# schematic.net
KiCad netlist of a schematic drawn in Altium Designer
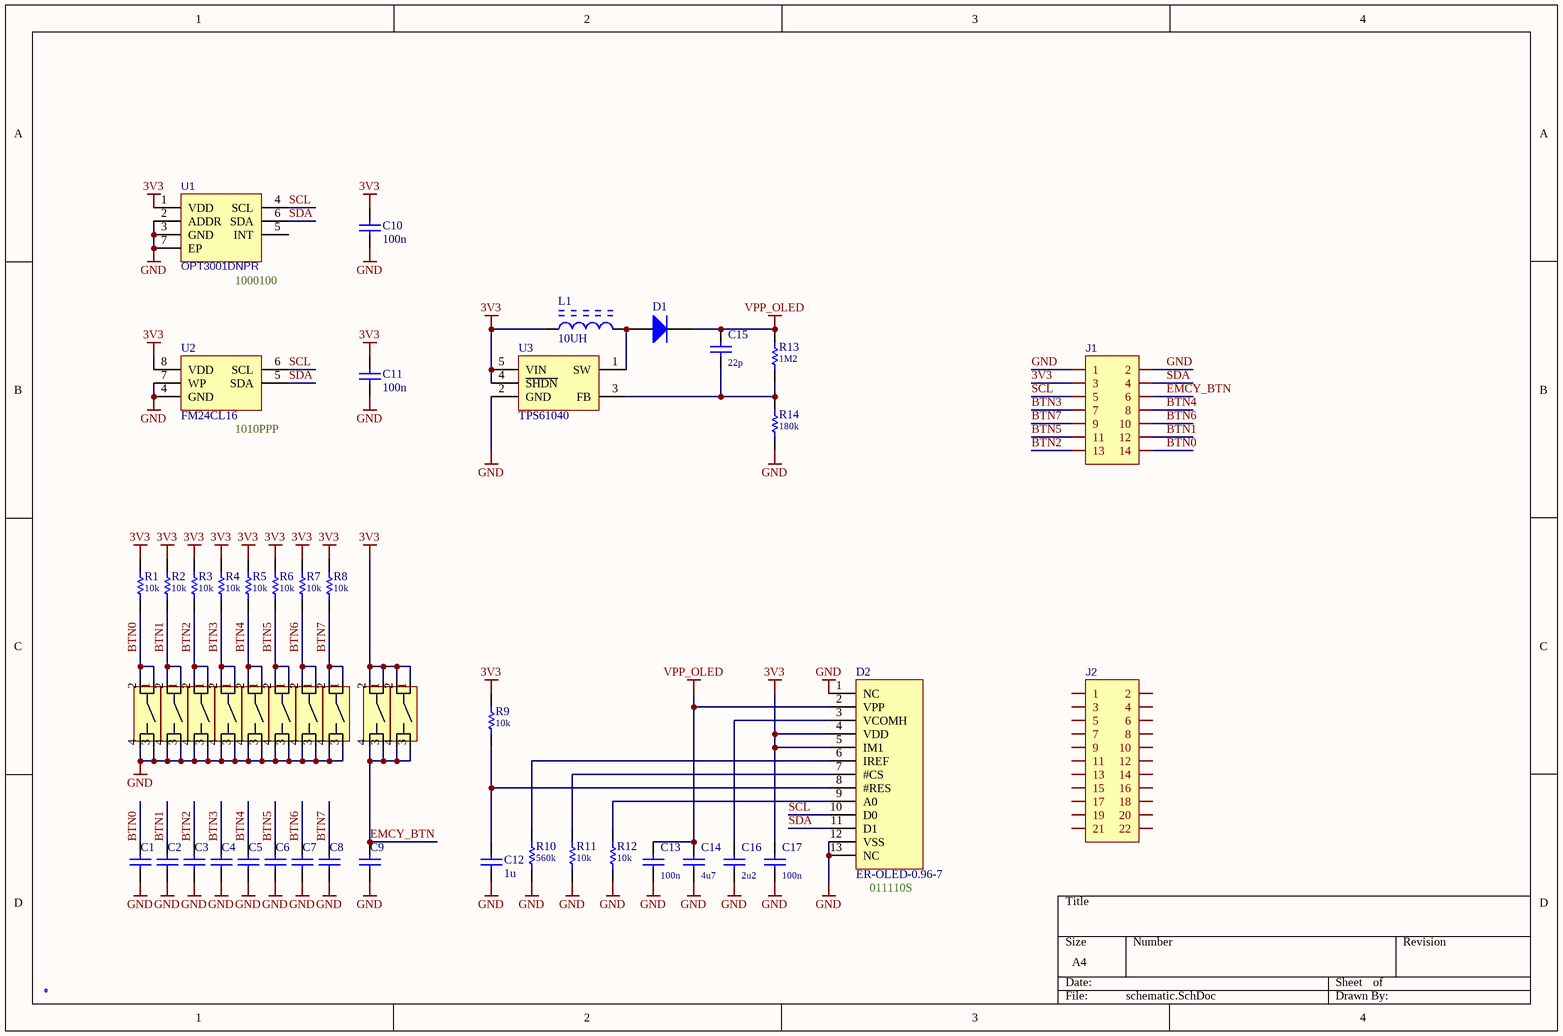
[diagram p0: schematic.SchDoc]

(export (version "E")
  (design (tool "Eeschema 10.0.6"))
  (components
    (comp (ref "C1")
      (value "100n")
      (footprint "C0402")
      (libsource (lib "Miscellaneous Devices") (part "Cap"))
    )
    (comp (ref "C2")
      (value "100n")
      (footprint "C0402")
      (libsource (lib "Miscellaneous Devices") (part "Cap"))
    )
    (comp (ref "C3")
      (value "100n")
      (footprint "C0402")
      (libsource (lib "Miscellaneous Devices") (part "Cap"))
    )
    (comp (ref "C4")
      (value "100n")
      (footprint "C0402")
      (libsource (lib "Miscellaneous Devices") (part "Cap"))
    )
    (comp (ref "C5")
      (value "100n")
      (footprint "C0402")
      (libsource (lib "Miscellaneous Devices") (part "Cap"))
    )
    (comp (ref "C6")
      (value "100n")
      (footprint "C0402")
      (libsource (lib "Miscellaneous Devices") (part "Cap"))
    )
    (comp (ref "C7")
      (value "100n")
      (footprint "C0402")
      (libsource (lib "Miscellaneous Devices") (part "Cap"))
    )
    (comp (ref "C8")
      (value "100n")
      (footprint "C0402")
      (libsource (lib "Miscellaneous Devices") (part "Cap"))
    )
    (comp (ref "C9")
      (value "100n")
      (footprint "C0402")
      (libsource (lib "Miscellaneous Devices") (part "Cap"))
    )
    (comp (ref "C10")
      (value "100n")
      (footprint "C0402")
      (libsource (lib "Miscellaneous Devices") (part "Cap"))
    )
    (comp (ref "C11")
      (value "100n")
      (footprint "C0402")
      (libsource (lib "Miscellaneous Devices") (part "Cap"))
    )
    (comp (ref "C12") (value "1u") (footprint "C0603") (libsource (lib "Miscellaneous Devices") (part "Cap")))
    (comp (ref "C13")
      (value "100n")
      (footprint "C0603")
      (libsource (lib "Miscellaneous Devices") (part "CAP"))
    )
    (comp (ref "C14")
      (value "4u7")
      (footprint "C0805")
      (libsource (lib "Miscellaneous Devices") (part "CAP"))
    )
    (comp (ref "C15")
      (value "22p")
      (footprint "C0603")
      (libsource (lib "Miscellaneous Devices") (part "CAP"))
    )
    (comp (ref "C16")
      (value "2u2")
      (footprint "C0603")
      (libsource (lib "Miscellaneous Devices") (part "CAP"))
    )
    (comp (ref "C17")
      (value "100n")
      (footprint "C0603")
      (libsource (lib "Miscellaneous Devices") (part "CAP"))
    )
    (comp (ref "D1")
      (value "~")
      (footprint "SOD-323")
      (libsource (lib "Miscellaneous Devices") (part "US1M-13-F"))
    )
    (comp (ref "D2")
      (value "ER-OLED-0.96-7")
      (footprint "pico_oled_1.3")
      (libsource (lib "Schlib2") (part "Component_1"))
    )
    (comp (ref "J1") (value "~") (footprint "HDR-2X7-P2.00") (libsource (lib "Schlib1") (part "HDR 2X7")))
    (comp (ref "J2") (value "~") (footprint "HDR-2X11-P2.00") (libsource (lib "Schlib1") (part "HDR 2X11")))
    (comp (ref "L1")
      (value "10UH")
      (footprint "IND_SDE0403A_4X4MM")
      (description "10uH 1A 2520")
      (libsource (lib "Miscellaneous Devices") (part "SRN3015-100M"))
    )
    (comp (ref "LOGO1") (value "LOGO") (footprint "LOGO") (libsource (lib "Schlib1") (part "LOGO")))
    (comp (ref "R1") (value "10k") (footprint "R0603") (libsource (lib "Miscellaneous Devices") (part "RES")))
    (comp (ref "R2") (value "10k") (footprint "R0603") (libsource (lib "Miscellaneous Devices") (part "RES")))
    (comp (ref "R3") (value "10k") (footprint "R0603") (libsource (lib "Miscellaneous Devices") (part "RES")))
    (comp (ref "R4") (value "10k") (footprint "R0603") (libsource (lib "Miscellaneous Devices") (part "RES")))
    (comp (ref "R5") (value "10k") (footprint "R0603") (libsource (lib "Miscellaneous Devices") (part "RES")))
    (comp (ref "R6") (value "10k") (footprint "R0603") (libsource (lib "Miscellaneous Devices") (part "RES")))
    (comp (ref "R7") (value "10k") (footprint "R0603") (libsource (lib "Miscellaneous Devices") (part "RES")))
    (comp (ref "R8") (value "10k") (footprint "R0603") (libsource (lib "Miscellaneous Devices") (part "RES")))
    (comp (ref "R9")
      (value "10k")
      (footprint "R0603")
      (description "10k 0603")
      (libsource (lib "RR_Passive") (part "RES"))
    )
    (comp (ref "R10")
      (value "560k")
      (footprint "R0603")
      (libsource (lib "Miscellaneous Devices") (part "RES"))
    )
    (comp (ref "R11")
      (value "10k")
      (footprint "R0603")
      (description "10k 0603")
      (libsource (lib "RR_Passive") (part "RES"))
    )
    (comp (ref "R12")
      (value "10k")
      (footprint "R0603")
      (description "10k 0603")
      (libsource (lib "RR_Passive") (part "RES"))
    )
    (comp (ref "R13")
      (value "1M2")
      (footprint "R0603")
      (libsource (lib "Miscellaneous Devices") (part "RES"))
    )
    (comp (ref "R14")
      (value "180k")
      (footprint "R0603")
      (libsource (lib "Miscellaneous Devices") (part "RES"))
    )
    (comp (ref "SW1")
      (value "PTS810SJS250")
      (footprint "BTN_PTS810")
      (fields (field (name "LCSC PART NUMBER") "C221896"))
      (libsource (lib "Miscellaneous Devices") (part "Component_1"))
    )
    (comp (ref "SW2")
      (value "PTS810SJS250")
      (footprint "BTN_PTS810")
      (fields (field (name "LCSC PART NUMBER") "C221896"))
      (libsource (lib "Miscellaneous Devices") (part "Component_1"))
    )
    (comp (ref "SW3")
      (value "PTS810SJS250")
      (footprint "BTN_PTS810")
      (fields (field (name "LCSC PART NUMBER") "C221896"))
      (libsource (lib "Miscellaneous Devices") (part "Component_1"))
    )
    (comp (ref "SW4")
      (value "PTS810SJS250")
      (footprint "BTN_PTS810")
      (fields (field (name "LCSC PART NUMBER") "C221896"))
      (libsource (lib "Miscellaneous Devices") (part "Component_1"))
    )
    (comp (ref "SW5")
      (value "PTS810SJS250")
      (footprint "BTN_PTS810")
      (fields (field (name "LCSC PART NUMBER") "C221896"))
      (libsource (lib "Miscellaneous Devices") (part "Component_1"))
    )
    (comp (ref "SW6")
      (value "PTS810SJS250")
      (footprint "BTN_PTS810")
      (fields (field (name "LCSC PART NUMBER") "C221896"))
      (libsource (lib "Miscellaneous Devices") (part "Component_1"))
    )
    (comp (ref "SW7")
      (value "PTS810SJS250")
      (footprint "BTN_PTS810")
      (fields (field (name "LCSC PART NUMBER") "C221896"))
      (libsource (lib "Miscellaneous Devices") (part "Component_1"))
    )
    (comp (ref "SW8")
      (value "PTS810SJS250")
      (footprint "BTN_PTS810")
      (fields (field (name "LCSC PART NUMBER") "C221896"))
      (libsource (lib "Miscellaneous Devices") (part "Component_1"))
    )
    (comp (ref "SW9")
      (value "PTS810SJS250")
      (footprint "BTN_PTS810")
      (fields (field (name "LCSC PART NUMBER") "C221896"))
      (libsource (lib "Miscellaneous Devices") (part "Component_1"))
    )
    (comp (ref "SW10")
      (value "PTS810SJS250")
      (footprint "BTN_PTS810")
      (fields (field (name "LCSC PART NUMBER") "C221896"))
      (libsource (lib "Miscellaneous Devices") (part "Component_1"))
    )
    (comp (ref "U1")
      (value "OPT3001DNPR")
      (footprint "USON6_L2.1-W2.1-P0.65-BL-EP")
      (fields (field (name "LCSC PART NUMBER") "C90462"))
      (libsource (lib "Schlib1") (part "OPT3001DNPR"))
    )
    (comp (ref "U2") (value "FM24CL16") (footprint "SOIC-8") (libsource (lib "Schlib1") (part "MB85RC16")))
    (comp (ref "U3")
      (value "TPS61040")
      (footprint "SOT-23-5")
      (libsource (lib "Miscellaneous Devices") (part "LM27313XMFX"))
    )
  )
  (nets
    (net (code "1") (name "/BTN0") (class "Default")
      (node (ref "C1") (pin "2") (pinfunction "2_2") (pintype "passive"))
      (node (ref "J1") (pin "14") (pinfunction "14_14") (pintype "passive"))
      (node (ref "R1") (pin "1") (pinfunction "1_1") (pintype "passive"))
      (node (ref "SW1") (pin "1") (pinfunction "1_1") (pintype "passive"))
      (node (ref "SW1") (pin "2") (pinfunction "2_2") (pintype "passive"))
    )
    (net (code "2") (name "/BTN1") (class "Default")
      (node (ref "C2") (pin "2") (pinfunction "2_2") (pintype "passive"))
      (node (ref "J1") (pin "12") (pinfunction "12_12") (pintype "passive"))
      (node (ref "R2") (pin "1") (pinfunction "1_1") (pintype "passive"))
      (node (ref "SW2") (pin "1") (pinfunction "1_1") (pintype "passive"))
      (node (ref "SW2") (pin "2") (pinfunction "2_2") (pintype "passive"))
    )
    (net (code "3") (name "/BTN2") (class "Default")
      (node (ref "C3") (pin "2") (pinfunction "2_2") (pintype "passive"))
      (node (ref "J1") (pin "13") (pinfunction "13_13") (pintype "passive"))
      (node (ref "R3") (pin "1") (pinfunction "1_1") (pintype "passive"))
      (node (ref "SW3") (pin "1") (pinfunction "1_1") (pintype "passive"))
      (node (ref "SW3") (pin "2") (pinfunction "2_2") (pintype "passive"))
    )
    (net (code "4") (name "/BTN3") (class "Default")
      (node (ref "C4") (pin "2") (pinfunction "2_2") (pintype "passive"))
      (node (ref "J1") (pin "7") (pinfunction "7_7") (pintype "passive"))
      (node (ref "R4") (pin "1") (pinfunction "1_1") (pintype "passive"))
      (node (ref "SW4") (pin "1") (pinfunction "1_1") (pintype "passive"))
      (node (ref "SW4") (pin "2") (pinfunction "2_2") (pintype "passive"))
    )
    (net (code "5") (name "/BTN4") (class "Default")
      (node (ref "C5") (pin "2") (pinfunction "2_2") (pintype "passive"))
      (node (ref "J1") (pin "8") (pinfunction "8_8") (pintype "passive"))
      (node (ref "R5") (pin "1") (pinfunction "1_1") (pintype "passive"))
      (node (ref "SW5") (pin "1") (pinfunction "1_1") (pintype "passive"))
      (node (ref "SW5") (pin "2") (pinfunction "2_2") (pintype "passive"))
    )
    (net (code "6") (name "/BTN5") (class "Default")
      (node (ref "C6") (pin "2") (pinfunction "2_2") (pintype "passive"))
      (node (ref "J1") (pin "11") (pinfunction "11_11") (pintype "passive"))
      (node (ref "R6") (pin "1") (pinfunction "1_1") (pintype "passive"))
      (node (ref "SW6") (pin "1") (pinfunction "1_1") (pintype "passive"))
      (node (ref "SW6") (pin "2") (pinfunction "2_2") (pintype "passive"))
    )
    (net (code "7") (name "/BTN6") (class "Default")
      (node (ref "C7") (pin "2") (pinfunction "2_2") (pintype "passive"))
      (node (ref "J1") (pin "10") (pinfunction "10_10") (pintype "passive"))
      (node (ref "R7") (pin "1") (pinfunction "1_1") (pintype "passive"))
      (node (ref "SW7") (pin "1") (pinfunction "1_1") (pintype "passive"))
      (node (ref "SW7") (pin "2") (pinfunction "2_2") (pintype "passive"))
    )
    (net (code "8") (name "/BTN7") (class "Default")
      (node (ref "C8") (pin "2") (pinfunction "2_2") (pintype "passive"))
      (node (ref "J1") (pin "9") (pinfunction "9_9") (pintype "passive"))
      (node (ref "R8") (pin "1") (pinfunction "1_1") (pintype "passive"))
      (node (ref "SW8") (pin "1") (pinfunction "1_1") (pintype "passive"))
      (node (ref "SW8") (pin "2") (pinfunction "2_2") (pintype "passive"))
    )
    (net (code "9") (name "/EMCY_BTN") (class "Default")
      (node (ref "C9") (pin "2") (pinfunction "2_2") (pintype "passive"))
      (node (ref "J1") (pin "6") (pinfunction "6_6") (pintype "passive"))
      (node (ref "SW10") (pin "3") (pinfunction "3_3") (pintype "passive"))
      (node (ref "SW10") (pin "4") (pinfunction "4_4") (pintype "passive"))
      (node (ref "SW9") (pin "3") (pinfunction "3_3") (pintype "passive"))
      (node (ref "SW9") (pin "4") (pinfunction "4_4") (pintype "passive"))
    )
    (net (code "10") (name "/SCL") (class "Default")
      (node (ref "D2") (pin "10") (pinfunction "D0_10") (pintype "passive"))
      (node (ref "J1") (pin "5") (pinfunction "5_5") (pintype "passive"))
      (node (ref "U1") (pin "4") (pinfunction "SCL_4") (pintype "passive"))
      (node (ref "U2") (pin "6") (pinfunction "SCL_6") (pintype "passive"))
    )
    (net (code "11") (name "/SDA") (class "Default")
      (node (ref "D2") (pin "11") (pinfunction "D1_11") (pintype "passive"))
      (node (ref "J1") (pin "4") (pinfunction "4_4") (pintype "passive"))
      (node (ref "U1") (pin "6") (pinfunction "SDA_6") (pintype "passive"))
      (node (ref "U2") (pin "5") (pinfunction "SDA_5") (pintype "passive"))
    )
    (net (code "12") (name "3V3") (class "Default")
      (node (ref "C10") (pin "2") (pinfunction "2_2") (pintype "passive"))
      (node (ref "C11") (pin "2") (pinfunction "2_2") (pintype "passive"))
      (node (ref "C17") (pin "1") (pinfunction "1_1") (pintype "passive"))
      (node (ref "D2") (pin "4") (pinfunction "VDD_4") (pintype "passive"))
      (node (ref "D2") (pin "5") (pinfunction "IM1_5") (pintype "passive"))
      (node (ref "J1") (pin "3") (pinfunction "3_3") (pintype "passive"))
      (node (ref "L1") (pin "1") (pinfunction "1_1") (pintype "passive"))
      (node (ref "R1") (pin "2") (pinfunction "2_2") (pintype "passive"))
      (node (ref "R2") (pin "2") (pinfunction "2_2") (pintype "passive"))
      (node (ref "R3") (pin "2") (pinfunction "2_2") (pintype "passive"))
      (node (ref "R4") (pin "2") (pinfunction "2_2") (pintype "passive"))
      (node (ref "R5") (pin "2") (pinfunction "2_2") (pintype "passive"))
      (node (ref "R6") (pin "2") (pinfunction "2_2") (pintype "passive"))
      (node (ref "R7") (pin "2") (pinfunction "2_2") (pintype "passive"))
      (node (ref "R8") (pin "2") (pinfunction "2_2") (pintype "passive"))
      (node (ref "R9") (pin "2") (pinfunction "2_2") (pintype "passive"))
      (node (ref "SW10") (pin "1") (pinfunction "1_1") (pintype "passive"))
      (node (ref "SW10") (pin "2") (pinfunction "2_2") (pintype "passive"))
      (node (ref "SW9") (pin "1") (pinfunction "1_1") (pintype "passive"))
      (node (ref "SW9") (pin "2") (pinfunction "2_2") (pintype "passive"))
      (node (ref "U1") (pin "1") (pinfunction "VDD_1") (pintype "passive"))
      (node (ref "U2") (pin "8") (pinfunction "VDD_8") (pintype "passive"))
      (node (ref "U3") (pin "4") (pinfunction "~{SHDN}_4") (pintype "passive"))
      (node (ref "U3") (pin "5") (pinfunction "VIN_5") (pintype "passive"))
    )
    (net (code "13") (name "GND") (class "Default")
      (node (ref "C1") (pin "1") (pinfunction "1_1") (pintype "passive"))
      (node (ref "C10") (pin "1") (pinfunction "1_1") (pintype "passive"))
      (node (ref "C11") (pin "1") (pinfunction "1_1") (pintype "passive"))
      (node (ref "C12") (pin "1") (pinfunction "1_1") (pintype "passive"))
      (node (ref "C13") (pin "2") (pinfunction "2_2") (pintype "passive"))
      (node (ref "C14") (pin "2") (pinfunction "2_2") (pintype "passive"))
      (node (ref "C16") (pin "2") (pinfunction "2_2") (pintype "passive"))
      (node (ref "C17") (pin "2") (pinfunction "2_2") (pintype "passive"))
      (node (ref "C2") (pin "1") (pinfunction "1_1") (pintype "passive"))
      (node (ref "C3") (pin "1") (pinfunction "1_1") (pintype "passive"))
      (node (ref "C4") (pin "1") (pinfunction "1_1") (pintype "passive"))
      (node (ref "C5") (pin "1") (pinfunction "1_1") (pintype "passive"))
      (node (ref "C6") (pin "1") (pinfunction "1_1") (pintype "passive"))
      (node (ref "C7") (pin "1") (pinfunction "1_1") (pintype "passive"))
      (node (ref "C8") (pin "1") (pinfunction "1_1") (pintype "passive"))
      (node (ref "C9") (pin "1") (pinfunction "1_1") (pintype "passive"))
      (node (ref "D2") (pin "1") (pinfunction "NC_1") (pintype "passive"))
      (node (ref "D2") (pin "12") (pinfunction "VSS_12") (pintype "passive"))
      (node (ref "D2") (pin "13") (pinfunction "NC_13") (pintype "passive"))
      (node (ref "J1") (pin "1") (pinfunction "1_1") (pintype "passive"))
      (node (ref "J1") (pin "2") (pinfunction "2_2") (pintype "passive"))
      (node (ref "R10") (pin "1") (pinfunction "1_1") (pintype "passive"))
      (node (ref "R11") (pin "1") (pinfunction "1_1") (pintype "passive"))
      (node (ref "R12") (pin "1") (pinfunction "1_1") (pintype "passive"))
      (node (ref "R14") (pin "1") (pinfunction "1_1") (pintype "passive"))
      (node (ref "SW1") (pin "3") (pinfunction "3_3") (pintype "passive"))
      (node (ref "SW1") (pin "4") (pinfunction "4_4") (pintype "passive"))
      (node (ref "SW2") (pin "3") (pinfunction "3_3") (pintype "passive"))
      (node (ref "SW2") (pin "4") (pinfunction "4_4") (pintype "passive"))
      (node (ref "SW3") (pin "3") (pinfunction "3_3") (pintype "passive"))
      (node (ref "SW3") (pin "4") (pinfunction "4_4") (pintype "passive"))
      (node (ref "SW4") (pin "3") (pinfunction "3_3") (pintype "passive"))
      (node (ref "SW4") (pin "4") (pinfunction "4_4") (pintype "passive"))
      (node (ref "SW5") (pin "3") (pinfunction "3_3") (pintype "passive"))
      (node (ref "SW5") (pin "4") (pinfunction "4_4") (pintype "passive"))
      (node (ref "SW6") (pin "3") (pinfunction "3_3") (pintype "passive"))
      (node (ref "SW6") (pin "4") (pinfunction "4_4") (pintype "passive"))
      (node (ref "SW7") (pin "3") (pinfunction "3_3") (pintype "passive"))
      (node (ref "SW7") (pin "4") (pinfunction "4_4") (pintype "passive"))
      (node (ref "SW8") (pin "3") (pinfunction "3_3") (pintype "passive"))
      (node (ref "SW8") (pin "4") (pinfunction "4_4") (pintype "passive"))
      (node (ref "U1") (pin "2") (pinfunction "ADDR_2") (pintype "passive"))
      (node (ref "U1") (pin "3") (pinfunction "GND_3") (pintype "passive"))
      (node (ref "U1") (pin "7") (pinfunction "EP_7") (pintype "passive"))
      (node (ref "U2") (pin "4") (pinfunction "GND_4") (pintype "passive"))
      (node (ref "U2") (pin "7") (pinfunction "WP_7") (pintype "passive"))
      (node (ref "U3") (pin "2") (pinfunction "GND_2") (pintype "passive"))
    )
    (net (code "14") (name "Net-(D1-A)") (class "Default")
      (node (ref "D1") (pin "1") (pinfunction "A_1") (pintype "passive"))
      (node (ref "L1") (pin "2") (pinfunction "2_2") (pintype "passive"))
      (node (ref "U3") (pin "1") (pinfunction "SW_1") (pintype "passive"))
    )
    (net (code "15") (name "Net-(D2-#CS)") (class "Default")
      (node (ref "D2") (pin "7") (pinfunction "#CS_7") (pintype "passive"))
      (node (ref "R11") (pin "2") (pinfunction "2_2") (pintype "passive"))
    )
    (net (code "16") (name "Net-(D2-#RES)") (class "Default")
      (node (ref "C12") (pin "2") (pinfunction "2_2") (pintype "passive"))
      (node (ref "D2") (pin "8") (pinfunction "#RES_8") (pintype "passive"))
      (node (ref "R9") (pin "1") (pinfunction "1_1") (pintype "passive"))
    )
    (net (code "17") (name "Net-(D2-A0)") (class "Default")
      (node (ref "D2") (pin "9") (pinfunction "A0_9") (pintype "passive"))
      (node (ref "R12") (pin "2") (pinfunction "2_2") (pintype "passive"))
    )
    (net (code "18") (name "Net-(D2-IREF)") (class "Default")
      (node (ref "D2") (pin "6") (pinfunction "IREF_6") (pintype "passive"))
      (node (ref "R10") (pin "2") (pinfunction "2_2") (pintype "passive"))
    )
    (net (code "19") (name "Net-(D2-VCOMH)") (class "Default")
      (node (ref "C16") (pin "1") (pinfunction "1_1") (pintype "passive"))
      (node (ref "D2") (pin "3") (pinfunction "VCOMH_3") (pintype "passive"))
    )
    (net (code "20") (name "Net-(U3-FB)") (class "Default")
      (node (ref "C15") (pin "2") (pinfunction "2_2") (pintype "passive"))
      (node (ref "R13") (pin "1") (pinfunction "1_1") (pintype "passive"))
      (node (ref "R14") (pin "2") (pinfunction "2_2") (pintype "passive"))
      (node (ref "U3") (pin "3") (pinfunction "FB_3") (pintype "passive"))
    )
    (net (code "21") (name "VPP_OLED") (class "Default")
      (node (ref "C13") (pin "1") (pinfunction "1_1") (pintype "passive"))
      (node (ref "C14") (pin "1") (pinfunction "1_1") (pintype "passive"))
      (node (ref "C15") (pin "1") (pinfunction "1_1") (pintype "passive"))
      (node (ref "D1") (pin "2") (pinfunction "K_2") (pintype "passive"))
      (node (ref "D2") (pin "2") (pinfunction "VPP_2") (pintype "passive"))
      (node (ref "R13") (pin "2") (pinfunction "2_2") (pintype "passive"))
    )
    (net (code "22") (name "unconnected-(J2-Pad1)") (class "Default")
      (node (ref "J2") (pin "1") (pinfunction "1_1") (pintype "passive"))
    )
    (net (code "23") (name "unconnected-(J2-Pad2)") (class "Default")
      (node (ref "J2") (pin "2") (pinfunction "2_2") (pintype "passive"))
    )
    (net (code "24") (name "unconnected-(J2-Pad3)") (class "Default")
      (node (ref "J2") (pin "3") (pinfunction "3_3") (pintype "passive"))
    )
    (net (code "25") (name "unconnected-(J2-Pad4)") (class "Default")
      (node (ref "J2") (pin "4") (pinfunction "4_4") (pintype "passive"))
    )
    (net (code "26") (name "unconnected-(J2-Pad5)") (class "Default")
      (node (ref "J2") (pin "5") (pinfunction "5_5") (pintype "passive"))
    )
    (net (code "27") (name "unconnected-(J2-Pad6)") (class "Default")
      (node (ref "J2") (pin "6") (pinfunction "6_6") (pintype "passive"))
    )
    (net (code "28") (name "unconnected-(J2-Pad7)") (class "Default")
      (node (ref "J2") (pin "7") (pinfunction "7_7") (pintype "passive"))
    )
    (net (code "29") (name "unconnected-(J2-Pad8)") (class "Default")
      (node (ref "J2") (pin "8") (pinfunction "8_8") (pintype "passive"))
    )
    (net (code "30") (name "unconnected-(J2-Pad9)") (class "Default")
      (node (ref "J2") (pin "9") (pinfunction "9_9") (pintype "passive"))
    )
    (net (code "31") (name "unconnected-(J2-Pad10)") (class "Default")
      (node (ref "J2") (pin "10") (pinfunction "10_10") (pintype "passive"))
    )
    (net (code "32") (name "unconnected-(J2-Pad11)") (class "Default")
      (node (ref "J2") (pin "11") (pinfunction "11_11") (pintype "passive"))
    )
    (net (code "33") (name "unconnected-(J2-Pad12)") (class "Default")
      (node (ref "J2") (pin "12") (pinfunction "12_12") (pintype "passive"))
    )
    (net (code "34") (name "unconnected-(J2-Pad13)") (class "Default")
      (node (ref "J2") (pin "13") (pinfunction "13_13") (pintype "passive"))
    )
    (net (code "35") (name "unconnected-(J2-Pad14)") (class "Default")
      (node (ref "J2") (pin "14") (pinfunction "14_14") (pintype "passive"))
    )
    (net (code "36") (name "unconnected-(J2-Pad15)") (class "Default")
      (node (ref "J2") (pin "15") (pinfunction "15_15") (pintype "passive"))
    )
    (net (code "37") (name "unconnected-(J2-Pad16)") (class "Default")
      (node (ref "J2") (pin "16") (pinfunction "16_16") (pintype "passive"))
    )
    (net (code "38") (name "unconnected-(J2-Pad17)") (class "Default")
      (node (ref "J2") (pin "17") (pinfunction "17_17") (pintype "passive"))
    )
    (net (code "39") (name "unconnected-(J2-Pad18)") (class "Default")
      (node (ref "J2") (pin "18") (pinfunction "18_18") (pintype "passive"))
    )
    (net (code "40") (name "unconnected-(J2-Pad19)") (class "Default")
      (node (ref "J2") (pin "19") (pinfunction "19_19") (pintype "passive"))
    )
    (net (code "41") (name "unconnected-(J2-Pad20)") (class "Default")
      (node (ref "J2") (pin "20") (pinfunction "20_20") (pintype "passive"))
    )
    (net (code "42") (name "unconnected-(J2-Pad21)") (class "Default")
      (node (ref "J2") (pin "21") (pinfunction "21_21") (pintype "passive"))
    )
    (net (code "43") (name "unconnected-(J2-Pad22)") (class "Default")
      (node (ref "J2") (pin "22") (pinfunction "22_22") (pintype "passive"))
    )
    (net (code "44") (name "unconnected-(U1-INT-Pad5)") (class "Default")
      (node (ref "U1") (pin "5") (pinfunction "INT_5") (pintype "passive"))
    )
  )
)
